# OSSI-1_Beacon_2.net
KiCad netlist of a schematic drawn in Altium Designer
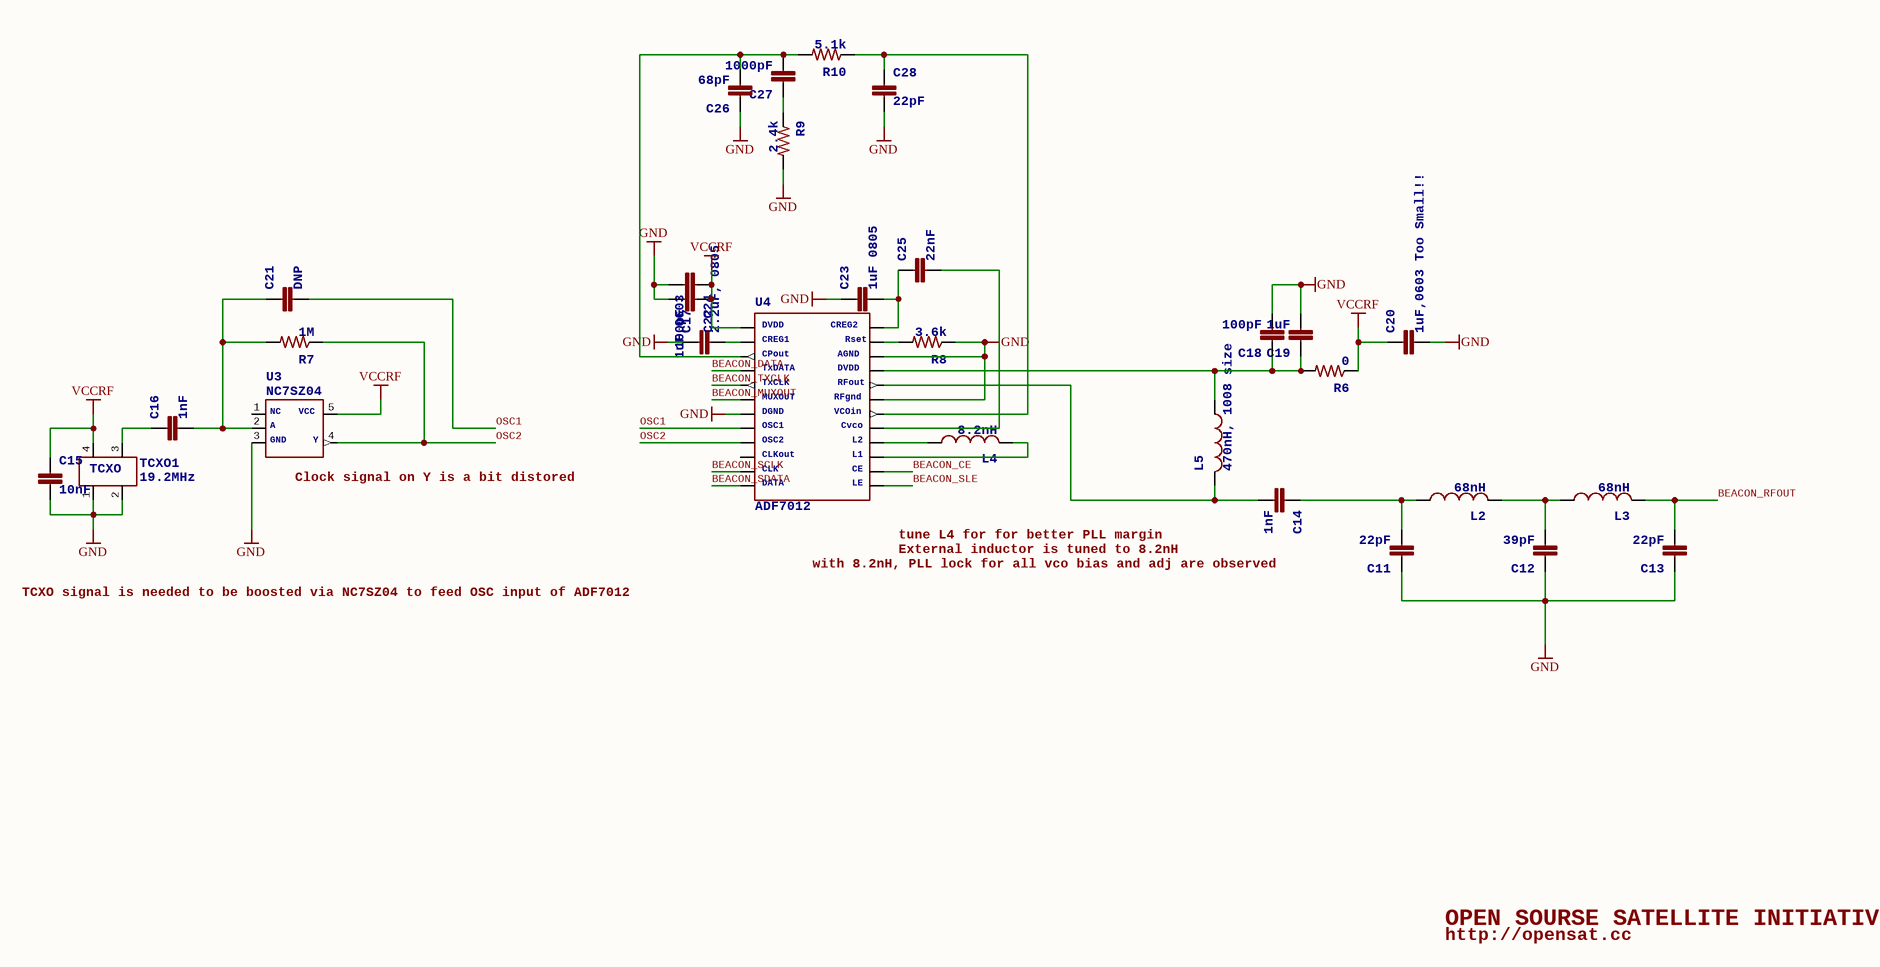
[diagram p0: OSSI-1 Beacon_2.SchDoc]

(export (version "E")
  (design (tool "Eeschema 10.0.6"))
  (components
    (comp (ref "C11")
      (value "22pF")
      (footprint "C0603(1608)")
      (fields (field (name ">NAME") "C11") (field (name ">VALUE") "22pF"))
      (libsource (lib "") (part "C0603(1608)_2"))
    )
    (comp (ref "C12")
      (value "39pF")
      (footprint "C0603(1608)")
      (fields (field (name ">NAME") "C12") (field (name ">VALUE") "39pF"))
      (libsource (lib "") (part "C0603(1608)_2"))
    )
    (comp (ref "C13")
      (value "22pF")
      (footprint "C0603(1608)")
      (fields (field (name ">NAME") "C13") (field (name ">VALUE") "22pF"))
      (libsource (lib "") (part "C0603(1608)_2"))
    )
    (comp (ref "C14")
      (value "1nF")
      (footprint "C0603(1608)")
      (fields (field (name ">NAME") "C14") (field (name ">VALUE") "1nF"))
      (libsource (lib "OSSI") (part "C0603(1608)"))
    )
    (comp (ref "C15")
      (value "10nF")
      (footprint "C0603(1608)")
      (fields (field (name ">NAME") "C15") (field (name ">VALUE") "10nF"))
      (libsource (lib "") (part "C0603(1608)_3"))
    )
    (comp (ref "C16")
      (value "1nF")
      (footprint "C0603(1608)")
      (fields (field (name ">NAME") "C16") (field (name ">VALUE") "1nF"))
      (libsource (lib "") (part "C0603(1608)_1"))
    )
    (comp (ref "C17")
      (value "2.2uF, 0805")
      (footprint "C0805(2012)")
      (fields (field (name ">NAME") "C17") (field (name ">VALUE") "2.2uF, 0805"))
      (libsource (lib "OSSI") (part "C0805(2012)"))
    )
    (comp (ref "C18")
      (value "100pF")
      (footprint "C0603(1608)")
      (fields (field (name ">NAME") "C18") (field (name ">VALUE") "100pF"))
      (libsource (lib "") (part "C0603(1608)_2"))
    )
    (comp (ref "C19")
      (value "1uF")
      (footprint "C0603(1608)")
      (fields (field (name ">NAME") "C19") (field (name ">VALUE") "1uF"))
      (libsource (lib "") (part "C0603(1608)_2"))
    )
    (comp (ref "C20")
      (value "1uF,0603 Too Small!!")
      (footprint "C0603(1608)")
      (fields (field (name ">NAME") "C20") (field (name ">VALUE") "1uF,0603 Too Small!!"))
      (libsource (lib "") (part "C0603(1608)_1"))
    )
    (comp (ref "C21")
      (value "DNP")
      (footprint "C0603(1608)")
      (fields (field (name ">NAME") "C21") (field (name ">VALUE") "DNP"))
      (libsource (lib "") (part "C0603(1608)_1"))
    )
    (comp (ref "C22")
      (value "100pF")
      (footprint "C0603(1608)")
      (fields (field (name ">NAME") "C22") (field (name ">VALUE") "100pF"))
      (libsource (lib "OSSI") (part "C0603(1608)"))
    )
    (comp (ref "C23")
      (value "1uF 0805")
      (footprint "C0805(2012)")
      (fields (field (name ">NAME") "C23") (field (name ">VALUE") "1uF 0805"))
      (libsource (lib "OSSI") (part "C0805(2012)"))
    )
    (comp (ref "C24")
      (value "1uF,0603")
      (footprint "C0603(1608)")
      (fields (field (name ">NAME") "C24") (field (name ">VALUE") "1uF,0603"))
      (libsource (lib "OSSI") (part "C0603(1608)"))
    )
    (comp (ref "C25")
      (value "22nF")
      (footprint "C0603(1608)")
      (fields (field (name ">NAME") "C25") (field (name ">VALUE") "22nF"))
      (libsource (lib "") (part "C0603(1608)_1"))
    )
    (comp (ref "C26")
      (value "68pF")
      (footprint "C0603(1608)")
      (fields (field (name ">NAME") "C26") (field (name ">VALUE") "68pF"))
      (libsource (lib "") (part "C0603(1608)_2"))
    )
    (comp (ref "C27")
      (value "1000pF")
      (footprint "C0603(1608)")
      (fields (field (name ">NAME") "C27") (field (name ">VALUE") "1000pF"))
      (libsource (lib "") (part "C0603(1608)_2"))
    )
    (comp (ref "C28")
      (value "22pF")
      (footprint "C0603(1608)")
      (fields (field (name ">NAME") "C28") (field (name ">VALUE") "22pF"))
      (libsource (lib "") (part "C0603(1608)_3"))
    )
    (comp (ref "L2")
      (value "68nH")
      (footprint "L0603(1608)")
      (fields (field (name ">NAME") "L2") (field (name ">VALUE") "68nH"))
      (libsource (lib "OSSI") (part "L0603(1608)"))
    )
    (comp (ref "L3")
      (value "68nH")
      (footprint "L0603(1608)")
      (fields (field (name ">NAME") "L3") (field (name ">VALUE") "68nH"))
      (libsource (lib "OSSI") (part "L0603(1608)"))
    )
    (comp (ref "L4")
      (value "8.2nH")
      (footprint "L0603(1608)")
      (fields (field (name ">NAME") "L4") (field (name ">VALUE") "8.2nH"))
      (libsource (lib "OSSI") (part "L0603(1608)"))
    )
    (comp (ref "L5")
      (value "470nH, 1008 size")
      (footprint "L1008(2520)")
      (fields (field (name ">NAME") "L5") (field (name ">VALUE") "470nH, 1008 size"))
      (libsource (lib "OSSI") (part "L1008(2502)"))
    )
    (comp (ref "R6")
      (value "0")
      (footprint "R0603(1608)")
      (fields (field (name ">NAME") "R6") (field (name ">VALUE") "0"))
      (libsource (lib "OSSI") (part "R0603(1608)"))
    )
    (comp (ref "R7")
      (value "1M")
      (footprint "R0603(1608)")
      (fields (field (name ">NAME") "R7") (field (name ">VALUE") "1M"))
      (libsource (lib "OSSI") (part "R0603(1608)"))
    )
    (comp (ref "R8")
      (value "3.6k")
      (footprint "R0603(1608)")
      (fields (field (name ">NAME") "R8") (field (name ">VALUE") "3.6k"))
      (libsource (lib "OSSI") (part "R0603(1608)"))
    )
    (comp (ref "R9")
      (value "2.4k")
      (footprint "R0603(1608)")
      (fields (field (name ">NAME") "R9") (field (name ">VALUE") "2.4k"))
      (libsource (lib "OSSI") (part "R0603(1608)"))
    )
    (comp (ref "R10")
      (value "5.1k")
      (footprint "R0603(1608)")
      (fields (field (name ">NAME") "R10") (field (name ">VALUE") "5.1k"))
      (libsource (lib "OSSI") (part "R0603(1608)"))
    )
    (comp (ref "TCXO1")
      (value "19.2MHz")
      (footprint "TCXO_M532")
      (fields (field (name "TCXO") "TCXO") (field (name ">NAME") "TCXO1") (field (name ">VALUE") "19.2MHz"))
      (libsource (lib "OSSI") (part "TCXO-M532"))
    )
    (comp (ref "U3")
      (value "NC7SZ04")
      (footprint "SC70-5")
      (description "UHS Inverter NC7SZ04")
      (fields
        (field (name ">NAME") "U3")
        (field (name ">VALUE") "NC7SZ04")
        (field (name "NC") "NC")
        (field (name "A") "A")
        (field (name "GND") "GND")
        (field (name "VCC") "VCC")
        (field (name "Y") "Y")
      )
      (libsource (lib "OSSI") (part "NC7SZ04"))
    )
    (comp (ref "U4")
      (value "ADF7012")
      (footprint "TSSOP24")
      (fields
        (field (name ">NAME") "U4")
        (field (name ">VALUE") "ADF7012")
        (field (name "DVDD") "DVDD")
        (field (name "CREG1") "CREG1")
        (field (name "CPOUT") "CPout")
        (field (name "TXDATA") "TxDATA")
        (field (name "MUXOUT") "MUXOUT")
        (field (name "DGND") "DGND")
        (field (name "OSC1") "OSC1")
        (field (name "OSC2") "OSC2")
        (field (name "CLKOUT") "CLKout")
        (field (name "CLK") "CLK")
        (field (name "DATA") "DATA")
        (field (name "TXCLK") "TxCLK")
        (field (name "LE") "LE")
        (field (name "CE") "CE")
        (field (name "L1") "L1")
        (field (name "L2") "L2")
        (field (name "CVCO") "Cvco")
        (field (name "VCOIN") "VCOin")
        (field (name "RFGND") "RFgnd")
        (field (name "RFOUT") "RFout")
        (field (name "DVDD_1") "DVDD")
        (field (name "AGND") "AGND")
        (field (name "RSET") "Rset")
        (field (name "CREG2") "CREG2")
      )
      (libsource (lib "OSSI") (part "ADF7012"))
    )
  )
  (nets
    (net (code "1") (name "/BEACON_CE") (class "Default")
      (node (ref "U4") (pin "14") (pinfunction "CE_14") (pintype "passive"))
    )
    (net (code "2") (name "/BEACON_DATA") (class "Default")
      (node (ref "U4") (pin "4") (pinfunction "TXDATA_4") (pintype "passive"))
    )
    (net (code "3") (name "/BEACON_MUXOUT") (class "Default")
      (node (ref "U4") (pin "6") (pinfunction "MUXOUT_6") (pintype "power_in"))
    )
    (net (code "4") (name "/BEACON_RFOUT") (class "Default")
      (node (ref "C13") (pin "2") (pinfunction "2_2") (pintype "passive"))
      (node (ref "L3") (pin "2") (pinfunction "2_2") (pintype "passive"))
    )
    (net (code "5") (name "/BEACON_SCLK") (class "Default")
      (node (ref "U4") (pin "11") (pinfunction "CLK_11") (pintype "passive"))
    )
    (net (code "6") (name "/BEACON_SDATA") (class "Default")
      (node (ref "U4") (pin "12") (pinfunction "DATA_12") (pintype "passive"))
    )
    (net (code "7") (name "/BEACON_SLE") (class "Default")
      (node (ref "U4") (pin "13") (pinfunction "LE_13") (pintype "passive"))
    )
    (net (code "8") (name "/BEACON_TXCLK") (class "Default")
      (node (ref "U4") (pin "5") (pinfunction "TXCLK_5") (pintype "output"))
    )
    (net (code "9") (name "/OSC1") (class "Default")
      (node (ref "C21") (pin "2") (pinfunction "2_2") (pintype "passive"))
      (node (ref "U4") (pin "8") (pinfunction "OSC1_8") (pintype "passive"))
    )
    (net (code "10") (name "/OSC2") (class "Default")
      (node (ref "R7") (pin "1") (pinfunction "1_1") (pintype "passive"))
      (node (ref "U3") (pin "4") (pinfunction "P$4_4") (pintype "output"))
      (node (ref "U4") (pin "9") (pinfunction "OSC2_9") (pintype "passive"))
    )
    (net (code "11") (name "GND") (class "Default")
      (node (ref "C11") (pin "1") (pinfunction "1_1") (pintype "passive"))
      (node (ref "C12") (pin "1") (pinfunction "1_1") (pintype "passive"))
      (node (ref "C13") (pin "1") (pinfunction "1_1") (pintype "passive"))
      (node (ref "C15") (pin "2") (pinfunction "2_2") (pintype "passive"))
      (node (ref "C17") (pin "1") (pinfunction "1_1") (pintype "passive"))
      (node (ref "C18") (pin "2") (pinfunction "2_2") (pintype "passive"))
      (node (ref "C19") (pin "2") (pinfunction "2_2") (pintype "passive"))
      (node (ref "C20") (pin "2") (pinfunction "2_2") (pintype "passive"))
      (node (ref "C22") (pin "2") (pinfunction "2_2") (pintype "passive"))
      (node (ref "C23") (pin "1") (pinfunction "1_1") (pintype "passive"))
      (node (ref "C24") (pin "2") (pinfunction "2_2") (pintype "passive"))
      (node (ref "C26") (pin "1") (pinfunction "1_1") (pintype "passive"))
      (node (ref "C28") (pin "2") (pinfunction "2_2") (pintype "passive"))
      (node (ref "R8") (pin "1") (pinfunction "1_1") (pintype "passive"))
      (node (ref "R9") (pin "2") (pinfunction "2_2") (pintype "passive"))
      (node (ref "TCXO1") (pin "1") (pinfunction "P$1_1") (pintype "passive"))
      (node (ref "TCXO1") (pin "2") (pinfunction "P$2_2") (pintype "passive"))
      (node (ref "U3") (pin "3") (pinfunction "P$3_3") (pintype "open_emitter"))
      (node (ref "U4") (pin "19") (pinfunction "RFGND_19") (pintype "power_in"))
      (node (ref "U4") (pin "22") (pinfunction "AGND_22") (pintype "power_in"))
      (node (ref "U4") (pin "7") (pinfunction "DGND_7") (pintype "passive"))
    )
    (net (code "12") (name "Net-(C11-Pad2)") (class "Default")
      (node (ref "C11") (pin "2") (pinfunction "2_2") (pintype "passive"))
      (node (ref "C14") (pin "1") (pinfunction "1_1") (pintype "passive"))
      (node (ref "L2") (pin "1") (pinfunction "1_1") (pintype "passive"))
    )
    (net (code "13") (name "Net-(C12-Pad2)") (class "Default")
      (node (ref "C12") (pin "2") (pinfunction "2_2") (pintype "passive"))
      (node (ref "L2") (pin "2") (pinfunction "2_2") (pintype "passive"))
      (node (ref "L3") (pin "1") (pinfunction "1_1") (pintype "passive"))
    )
    (net (code "14") (name "Net-(C27-Pad1)") (class "Default")
      (node (ref "C27") (pin "1") (pinfunction "1_1") (pintype "passive"))
      (node (ref "R9") (pin "1") (pinfunction "1_1") (pintype "passive"))
    )
    (net (code "15") (name "Net-(L5-1)") (class "Default")
      (node (ref "C18") (pin "1") (pinfunction "1_1") (pintype "passive"))
      (node (ref "C19") (pin "1") (pinfunction "1_1") (pintype "passive"))
      (node (ref "L5") (pin "P$1") (pinfunction "1_P$1") (pintype "passive"))
      (node (ref "R6") (pin "2") (pinfunction "2_2") (pintype "passive"))
      (node (ref "U4") (pin "21") (pinfunction "DVDD_2_21") (pintype "power_in"))
    )
    (net (code "16") (name "Net-(L5-2)") (class "Default")
      (node (ref "C14") (pin "2") (pinfunction "2_2") (pintype "passive"))
      (node (ref "L5") (pin "P$2") (pinfunction "2_P$2") (pintype "passive"))
      (node (ref "U4") (pin "20") (pinfunction "RFOUT_20") (pintype "output"))
    )
    (net (code "17") (name "Net-(TCXO1-P$3)") (class "Default")
      (node (ref "C16") (pin "1") (pinfunction "1_1") (pintype "passive"))
      (node (ref "TCXO1") (pin "3") (pinfunction "P$3_3") (pintype "passive"))
    )
    (net (code "18") (name "Net-(U3-P$2)") (class "Default")
      (node (ref "C16") (pin "2") (pinfunction "2_2") (pintype "passive"))
      (node (ref "C21") (pin "1") (pinfunction "1_1") (pintype "passive"))
      (node (ref "R7") (pin "2") (pinfunction "2_2") (pintype "passive"))
      (node (ref "U3") (pin "2") (pinfunction "P$2_2") (pintype "passive"))
    )
    (net (code "19") (name "Net-(U4-CPOUT)") (class "Default")
      (node (ref "C26") (pin "2") (pinfunction "2_2") (pintype "passive"))
      (node (ref "C27") (pin "2") (pinfunction "2_2") (pintype "passive"))
      (node (ref "R10") (pin "2") (pinfunction "2_2") (pintype "passive"))
      (node (ref "U4") (pin "3") (pinfunction "CPOUT_3") (pintype "output"))
    )
    (net (code "20") (name "Net-(U4-CREG1)") (class "Default")
      (node (ref "C17") (pin "2") (pinfunction "2_2") (pintype "passive"))
      (node (ref "U4") (pin "2") (pinfunction "CREG1_2") (pintype "passive"))
    )
    (net (code "21") (name "Net-(U4-CREG2)") (class "Default")
      (node (ref "C23") (pin "2") (pinfunction "2_2") (pintype "passive"))
      (node (ref "C25") (pin "1") (pinfunction "1_1") (pintype "passive"))
      (node (ref "U4") (pin "24") (pinfunction "CREG2_24") (pintype "passive"))
    )
    (net (code "22") (name "Net-(U4-CVCO)") (class "Default")
      (node (ref "C25") (pin "2") (pinfunction "2_2") (pintype "passive"))
      (node (ref "U4") (pin "17") (pinfunction "CVCO_17") (pintype "passive"))
    )
    (net (code "23") (name "Net-(U4-L1)") (class "Default")
      (node (ref "L4") (pin "2") (pinfunction "2_2") (pintype "passive"))
      (node (ref "U4") (pin "15") (pinfunction "L1_15") (pintype "passive"))
    )
    (net (code "24") (name "Net-(U4-L2)") (class "Default")
      (node (ref "L4") (pin "1") (pinfunction "1_1") (pintype "passive"))
      (node (ref "U4") (pin "16") (pinfunction "L2_16") (pintype "passive"))
    )
    (net (code "25") (name "Net-(U4-RSET)") (class "Default")
      (node (ref "R8") (pin "2") (pinfunction "2_2") (pintype "passive"))
      (node (ref "U4") (pin "23") (pinfunction "RSET_23") (pintype "passive"))
    )
    (net (code "26") (name "Net-(U4-VCOIN)") (class "Default")
      (node (ref "C28") (pin "1") (pinfunction "1_1") (pintype "passive"))
      (node (ref "R10") (pin "1") (pinfunction "1_1") (pintype "passive"))
      (node (ref "U4") (pin "18") (pinfunction "VCOIN_18") (pintype "output"))
    )
    (net (code "27") (name "VCCRF") (class "Default")
      (node (ref "C15") (pin "1") (pinfunction "1_1") (pintype "passive"))
      (node (ref "C20") (pin "1") (pinfunction "1_1") (pintype "passive"))
      (node (ref "C22") (pin "1") (pinfunction "1_1") (pintype "passive"))
      (node (ref "C24") (pin "1") (pinfunction "1_1") (pintype "passive"))
      (node (ref "R6") (pin "1") (pinfunction "1_1") (pintype "passive"))
      (node (ref "TCXO1") (pin "4") (pinfunction "P$4_4") (pintype "passive"))
      (node (ref "U3") (pin "5") (pinfunction "P$5_5") (pintype "power_in"))
      (node (ref "U4") (pin "1") (pinfunction "DVDD_1_1") (pintype "power_in"))
    )
    (net (code "28") (name "unconnected-(U3-P$1-Pad1)") (class "Default")
      (node (ref "U3") (pin "1") (pinfunction "P$1_1") (pintype "passive"))
    )
    (net (code "29") (name "unconnected-(U4-CLKOUT-Pad10)") (class "Default")
      (node (ref "U4") (pin "10") (pinfunction "CLKOUT_10") (pintype "passive"))
    )
  )
)
